# splitnblend.net
KiCad netlist of a schematic drawn in EAGLE
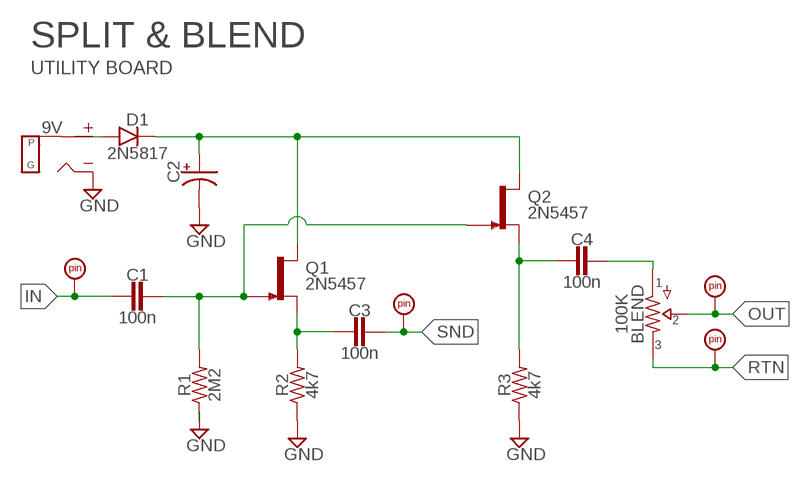
[diagram p0: schematic, sheet 1]

(export (version "E")
  (design (tool "Eeschema 10.0.6"))
  (components
    (comp (ref "9V")
      (value "DC_MONO")
      (footprint "eagle-import:DC")
      (libsource (lib "eagle-import") (part "DC_MONO"))
    )
    (comp (ref "BLEND")
      (value "100K")
      (footprint "eagle-import:16MM")
      (libsource (lib "eagle-import") (part "POTS16MM"))
    )
    (comp (ref "C1")
      (value "100n")
      (footprint "eagle-import:050X030_025_2")
      (libsource (lib "eagle-import") (part "CER/FILM2"))
    )
    (comp (ref "C2")
      (value "0501")
      (footprint "eagle-import:050_020_1")
      (libsource (lib "eagle-import") (part "0501"))
    )
    (comp (ref "C3")
      (value "100n")
      (footprint "eagle-import:050X030_025_2")
      (libsource (lib "eagle-import") (part "CER/FILM2"))
    )
    (comp (ref "C4")
      (value "100n")
      (footprint "eagle-import:050X030_025_2")
      (libsource (lib "eagle-import") (part "CER/FILM2"))
    )
    (comp (ref "D1")
      (value "2N5817")
      (footprint "eagle-import:DO41-3")
      (libsource (lib "eagle-import") (part "DO41.3"))
    )
    (comp (ref "IN")
      (value "PADSQR")
      (footprint "eagle-import:SQUARE")
      (libsource (lib "eagle-import") (part "PADSQR"))
    )
    (comp (ref "OUT")
      (value "PADSQR")
      (footprint "eagle-import:SQUARE")
      (libsource (lib "eagle-import") (part "PADSQR"))
    )
    (comp (ref "Q1")
      (value "2N5457")
      (footprint "eagle-import:TO92-")
      (libsource (lib "eagle-import") (part "2N5457"))
    )
    (comp (ref "Q2")
      (value "2N5457")
      (footprint "eagle-import:TO92-")
      (libsource (lib "eagle-import") (part "2N5457"))
    )
    (comp (ref "R1")
      (value "2M2")
      (footprint "eagle-import:R0207_3")
      (libsource (lib "eagle-import") (part "R_.3B"))
    )
    (comp (ref "R2")
      (value "4k7")
      (footprint "eagle-import:R0207_3")
      (libsource (lib "eagle-import") (part "R_.3B"))
    )
    (comp (ref "R3")
      (value "4k7")
      (footprint "eagle-import:R0207_3")
      (libsource (lib "eagle-import") (part "R_.3B"))
    )
    (comp (ref "RTN")
      (value "PADSQR")
      (footprint "eagle-import:SQUARE")
      (libsource (lib "eagle-import") (part "PADSQR"))
    )
    (comp (ref "SND")
      (value "PADSQR")
      (footprint "eagle-import:SQUARE")
      (libsource (lib "eagle-import") (part "PADSQR"))
    )
  )
  (nets
    (net (code "1") (name "GND") (class "Default")
      (node (ref "9V") (pin "S") (pinfunction "SLEEVE_S") (pintype "passive"))
      (node (ref "C2") (pin "-") (pinfunction "-_-") (pintype "passive"))
      (node (ref "R1") (pin "1") (pinfunction "1_1") (pintype "passive"))
      (node (ref "R2") (pin "1") (pinfunction "1_1") (pintype "passive"))
      (node (ref "R3") (pin "1") (pinfunction "1_1") (pintype "passive"))
    )
    (net (code "2") (name "IN") (class "Default")
      (node (ref "C1") (pin "2") (pinfunction "2_2") (pintype "passive"))
      (node (ref "IN") (pin "1") (pinfunction "P$1_1") (pintype "bidirectional"))
    )
    (net (code "3") (name "Net-(9V-TIP)") (class "Default")
      (node (ref "9V") (pin "T") (pinfunction "TIP_T") (pintype "passive"))
      (node (ref "D1") (pin "A") (pinfunction "A_A") (pintype "passive"))
    )
    (net (code "4") (name "Net-(BLEND-Pad1)") (class "Default")
      (node (ref "BLEND") (pin "1") (pinfunction "1_1") (pintype "passive"))
      (node (ref "C4") (pin "1") (pinfunction "1_1") (pintype "passive"))
    )
    (net (code "5") (name "Net-(Q1-D)") (class "Default")
      (node (ref "C2") (pin "+") (pinfunction "+_+") (pintype "passive"))
      (node (ref "D1") (pin "C") (pinfunction "C_C") (pintype "passive"))
      (node (ref "Q1") (pin "3") (pinfunction "D_3") (pintype "passive"))
      (node (ref "Q2") (pin "3") (pinfunction "D_3") (pintype "passive"))
    )
    (net (code "6") (name "Net-(Q1-G)") (class "Default")
      (node (ref "C1") (pin "1") (pinfunction "1_1") (pintype "passive"))
      (node (ref "Q1") (pin "1") (pinfunction "G_1") (pintype "passive"))
      (node (ref "Q2") (pin "1") (pinfunction "G_1") (pintype "passive"))
      (node (ref "R1") (pin "2") (pinfunction "2_2") (pintype "passive"))
    )
    (net (code "7") (name "Net-(Q1-S)") (class "Default")
      (node (ref "C3") (pin "2") (pinfunction "2_2") (pintype "passive"))
      (node (ref "Q1") (pin "2") (pinfunction "S_2") (pintype "passive"))
      (node (ref "R2") (pin "2") (pinfunction "2_2") (pintype "passive"))
    )
    (net (code "8") (name "Net-(Q2-S)") (class "Default")
      (node (ref "C4") (pin "2") (pinfunction "2_2") (pintype "passive"))
      (node (ref "Q2") (pin "2") (pinfunction "S_2") (pintype "passive"))
      (node (ref "R3") (pin "2") (pinfunction "2_2") (pintype "passive"))
    )
    (net (code "9") (name "OUT") (class "Default")
      (node (ref "BLEND") (pin "2") (pinfunction "2_2") (pintype "passive"))
      (node (ref "OUT") (pin "1") (pinfunction "P$1_1") (pintype "bidirectional"))
    )
    (net (code "10") (name "RTN") (class "Default")
      (node (ref "BLEND") (pin "3") (pinfunction "3_3") (pintype "passive"))
      (node (ref "RTN") (pin "1") (pinfunction "P$1_1") (pintype "bidirectional"))
    )
    (net (code "11") (name "SND") (class "Default")
      (node (ref "C3") (pin "1") (pinfunction "1_1") (pintype "passive"))
      (node (ref "SND") (pin "1") (pinfunction "P$1_1") (pintype "bidirectional"))
    )
  )
)
